# Isolated_DMX_Module.net
KiCad netlist of a schematic drawn in EAGLE
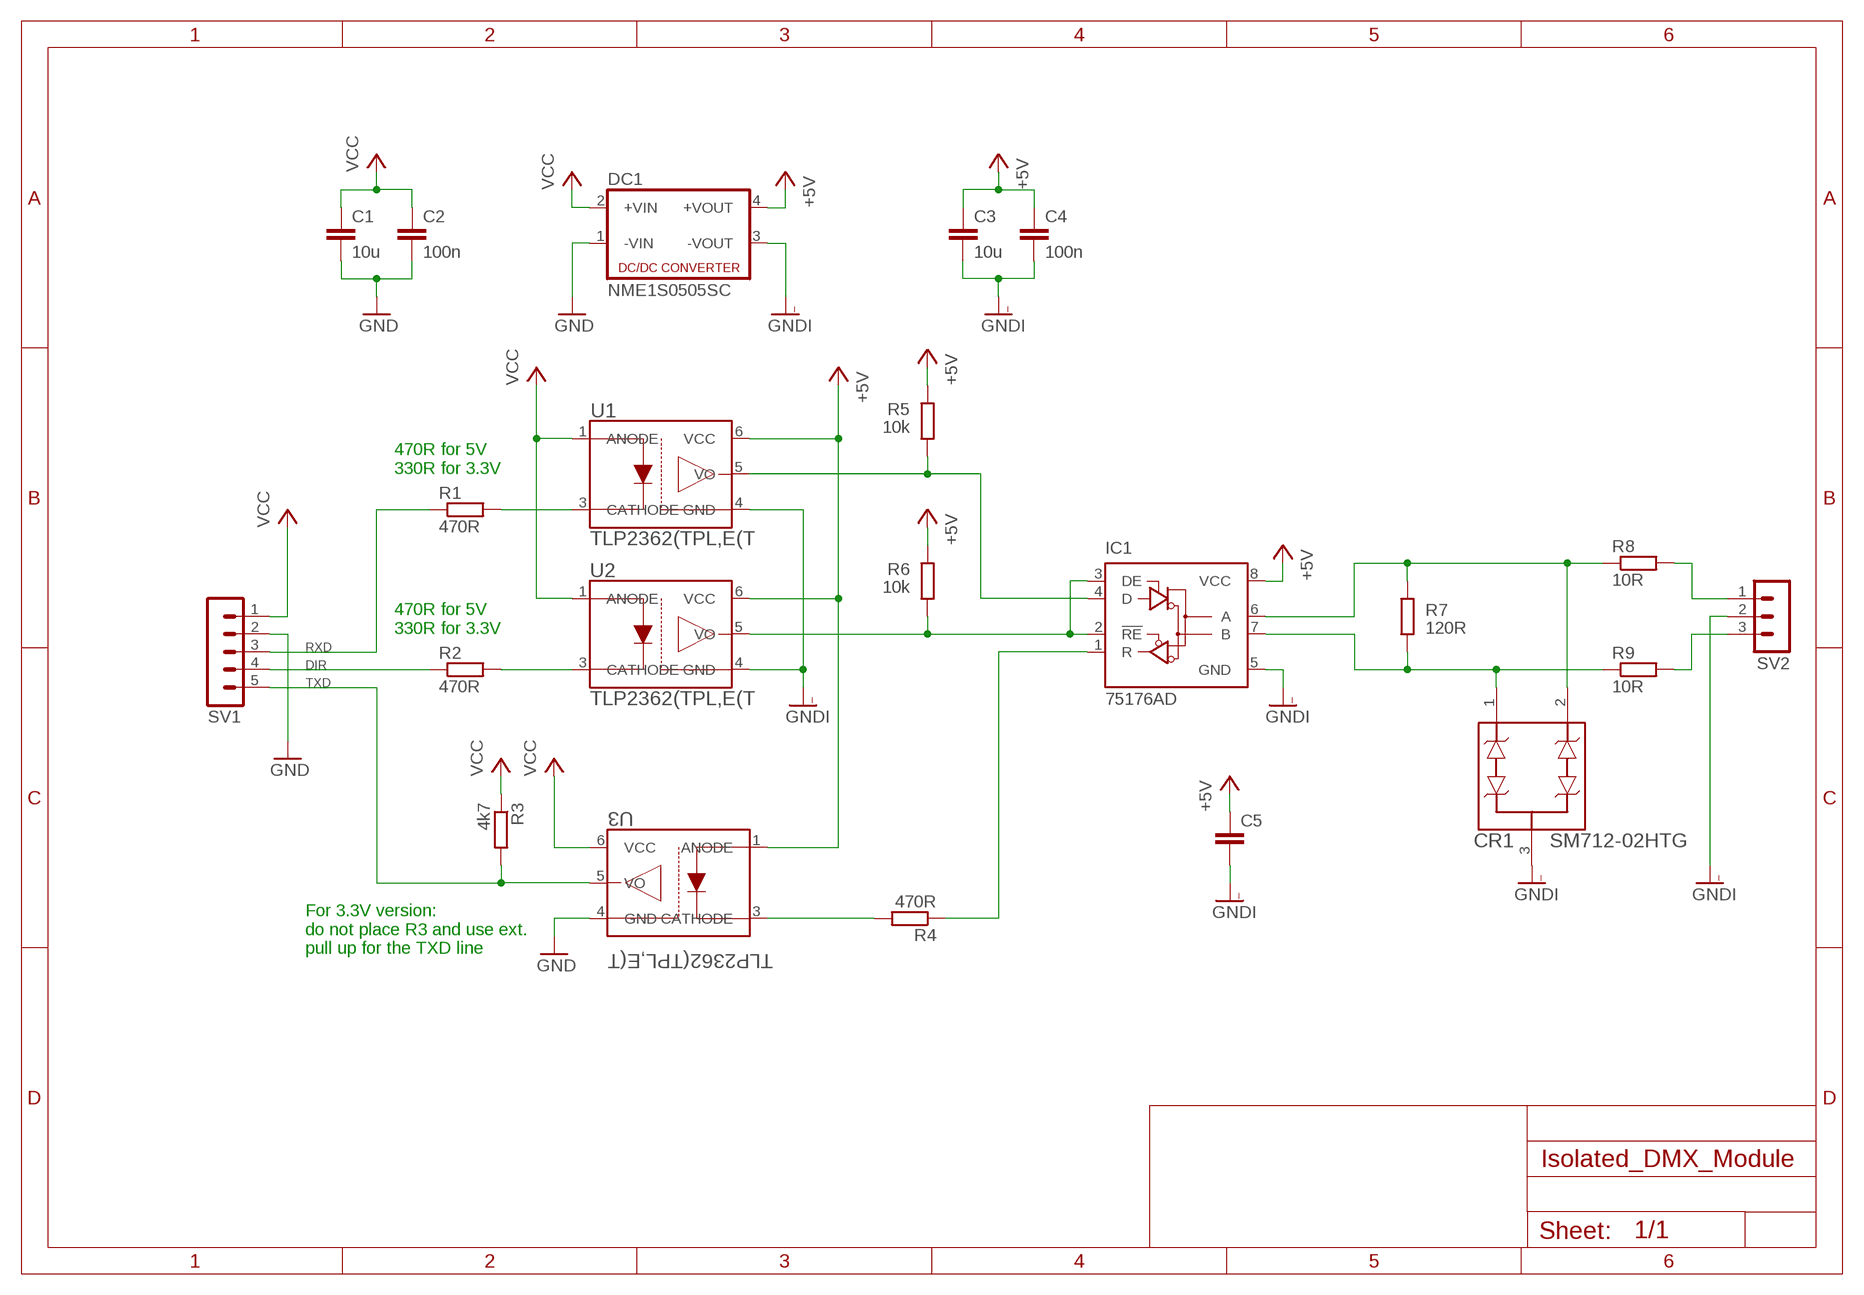
[diagram p0: schematic, sheet 1]

(export (version "E")
  (design (tool "Eeschema 10.0.6"))
  (components
    (comp (ref "C1")
      (value "10u")
      (footprint "eagle-import:C0805")
      (libsource (lib "eagle-import") (part "C-EUC0805"))
    )
    (comp (ref "C2")
      (value "100n")
      (footprint "eagle-import:C0603")
      (libsource (lib "eagle-import") (part "C-EUC0603"))
    )
    (comp (ref "C3")
      (value "10u")
      (footprint "eagle-import:C0805")
      (libsource (lib "eagle-import") (part "C-EUC0805"))
    )
    (comp (ref "C4")
      (value "100n")
      (footprint "eagle-import:C0603")
      (libsource (lib "eagle-import") (part "C-EUC0603"))
    )
    (comp (ref "C5")
      (value "C-EUC0603")
      (footprint "eagle-import:C0603")
      (libsource (lib "eagle-import") (part "C-EUC0603"))
    )
    (comp (ref "CR1")
      (value "SM712-02HTG")
      (footprint "eagle-import:SOT23-3_LTF")
      (fields (field (name "COPYRIGHT") "Copyright (C) 2024 Ultra Librarian. All rights reserved."))
      (libsource (lib "eagle-import") (part "SM712-02HTG"))
    )
    (comp (ref "DC1")
      (value "NME1S0505SC")
      (footprint "eagle-import:NME_FLAT")
      (libsource (lib "eagle-import") (part "NMEFLAT"))
    )
    (comp (ref "IC1")
      (value "75176AD")
      (footprint "eagle-import:D_R-PDSO-G8")
      (libsource (lib "eagle-import") (part "75176AD"))
    )
    (comp (ref "R1")
      (value "470R")
      (footprint "eagle-import:R0603")
      (libsource (lib "eagle-import") (part "R-EU_R0603"))
    )
    (comp (ref "R2")
      (value "470R")
      (footprint "eagle-import:R0603")
      (libsource (lib "eagle-import") (part "R-EU_R0603"))
    )
    (comp (ref "R3")
      (value "4k7")
      (footprint "eagle-import:R0603")
      (libsource (lib "eagle-import") (part "R-EU_R0603"))
    )
    (comp (ref "R4")
      (value "470R")
      (footprint "eagle-import:R0603")
      (libsource (lib "eagle-import") (part "R-EU_R0603"))
    )
    (comp (ref "R5")
      (value "10k")
      (footprint "eagle-import:R0603")
      (libsource (lib "eagle-import") (part "R-EU_R0603"))
    )
    (comp (ref "R6")
      (value "10k")
      (footprint "eagle-import:R0603")
      (libsource (lib "eagle-import") (part "R-EU_R0603"))
    )
    (comp (ref "R7")
      (value "120R")
      (footprint "eagle-import:R0603")
      (libsource (lib "eagle-import") (part "R-EU_R0603"))
    )
    (comp (ref "R8")
      (value "10R")
      (footprint "eagle-import:R0603")
      (libsource (lib "eagle-import") (part "R-EU_R0603"))
    )
    (comp (ref "R9")
      (value "10R")
      (footprint "eagle-import:R0603")
      (libsource (lib "eagle-import") (part "R-EU_R0603"))
    )
    (comp (ref "SV1")
      (value "MA05-1")
      (footprint "eagle-import:MA05-1")
      (libsource (lib "eagle-import") (part "MA05-1"))
    )
    (comp (ref "SV2")
      (value "MA03-1")
      (footprint "eagle-import:MA03-1")
      (libsource (lib "eagle-import") (part "MA03-1"))
    )
    (comp (ref "U1")
      (value "TLP2362(TPL,E(T")
      (footprint "eagle-import:11-4L1S_TOS")
      (fields (field (name "COPYRIGHT") "Copyright (C) 2024 Ultra Librarian. All rights reserved."))
      (libsource (lib "eagle-import") (part "TLP2362(TPL,E(T"))
    )
    (comp (ref "U2")
      (value "TLP2362(TPL,E(T")
      (footprint "eagle-import:11-4L1S_TOS")
      (fields (field (name "COPYRIGHT") "Copyright (C) 2024 Ultra Librarian. All rights reserved."))
      (libsource (lib "eagle-import") (part "TLP2362(TPL,E(T"))
    )
    (comp (ref "U3")
      (value "TLP2362(TPL,E(T")
      (footprint "eagle-import:11-4L1S_TOS")
      (fields (field (name "COPYRIGHT") "Copyright (C) 2024 Ultra Librarian. All rights reserved."))
      (libsource (lib "eagle-import") (part "TLP2362(TPL,E(T"))
    )
  )
  (nets
    (net (code "1") (name "+5V") (class "Default")
      (node (ref "C3") (pin "1") (pinfunction "1_1") (pintype "passive"))
      (node (ref "C4") (pin "1") (pinfunction "1_1") (pintype "passive"))
      (node (ref "C5") (pin "1") (pinfunction "1_1") (pintype "passive"))
      (node (ref "DC1") (pin "4") (pinfunction "+VOUT_4") (pintype "passive"))
      (node (ref "IC1") (pin "8") (pinfunction "VCC_8") (pintype "power_in"))
      (node (ref "R5") (pin "1") (pinfunction "1_1") (pintype "passive"))
      (node (ref "R6") (pin "1") (pinfunction "1_1") (pintype "passive"))
      (node (ref "U1") (pin "6") (pinfunction "VCC_6") (pintype "power_in"))
      (node (ref "U2") (pin "6") (pinfunction "VCC_6") (pintype "power_in"))
      (node (ref "U3") (pin "1") (pinfunction "ANODE_1") (pintype "passive"))
    )
    (net (code "2") (name "/DIR") (class "Default")
      (node (ref "R2") (pin "1") (pinfunction "1_1") (pintype "passive"))
      (node (ref "SV1") (pin "4") (pinfunction "4_4") (pintype "passive"))
    )
    (net (code "3") (name "/RXD") (class "Default")
      (node (ref "R1") (pin "1") (pinfunction "1_1") (pintype "passive"))
      (node (ref "SV1") (pin "3") (pinfunction "3_3") (pintype "passive"))
    )
    (net (code "4") (name "/TXD") (class "Default")
      (node (ref "R3") (pin "2") (pinfunction "2_2") (pintype "passive"))
      (node (ref "SV1") (pin "5") (pinfunction "5_5") (pintype "passive"))
      (node (ref "U3") (pin "5") (pinfunction "VO_5") (pintype "power_in"))
    )
    (net (code "5") (name "GND") (class "Default")
      (node (ref "C1") (pin "2") (pinfunction "2_2") (pintype "passive"))
      (node (ref "C2") (pin "2") (pinfunction "2_2") (pintype "passive"))
      (node (ref "DC1") (pin "1") (pinfunction "-VIN_1") (pintype "passive"))
      (node (ref "SV1") (pin "2") (pinfunction "2_2") (pintype "passive"))
      (node (ref "U3") (pin "4") (pinfunction "GND_4") (pintype "passive"))
    )
    (net (code "6") (name "GNDI") (class "Default")
      (node (ref "C3") (pin "2") (pinfunction "2_2") (pintype "passive"))
      (node (ref "C4") (pin "2") (pinfunction "2_2") (pintype "passive"))
      (node (ref "C5") (pin "2") (pinfunction "2_2") (pintype "passive"))
      (node (ref "CR1") (pin "3") (pinfunction "3_3") (pintype "passive"))
      (node (ref "DC1") (pin "3") (pinfunction "-VOUT_3") (pintype "passive"))
      (node (ref "IC1") (pin "5") (pinfunction "GND_5") (pintype "power_in"))
      (node (ref "SV2") (pin "2") (pinfunction "2_2") (pintype "passive"))
      (node (ref "U1") (pin "4") (pinfunction "GND_4") (pintype "passive"))
      (node (ref "U2") (pin "4") (pinfunction "GND_4") (pintype "passive"))
    )
    (net (code "7") (name "Net-(IC1-A)") (class "Default")
      (node (ref "CR1") (pin "2") (pinfunction "2_2") (pintype "passive"))
      (node (ref "IC1") (pin "6") (pinfunction "A_6") (pintype "output"))
      (node (ref "R7") (pin "1") (pinfunction "1_1") (pintype "passive"))
      (node (ref "R8") (pin "1") (pinfunction "1_1") (pintype "passive"))
    )
    (net (code "8") (name "Net-(IC1-B)") (class "Default")
      (node (ref "CR1") (pin "1") (pinfunction "1_1") (pintype "passive"))
      (node (ref "IC1") (pin "7") (pinfunction "B_7") (pintype "output"))
      (node (ref "R7") (pin "2") (pinfunction "2_2") (pintype "passive"))
      (node (ref "R9") (pin "1") (pinfunction "1_1") (pintype "passive"))
    )
    (net (code "9") (name "Net-(IC1-D)") (class "Default")
      (node (ref "IC1") (pin "4") (pinfunction "D_4") (pintype "input"))
      (node (ref "R5") (pin "2") (pinfunction "2_2") (pintype "passive"))
      (node (ref "U1") (pin "5") (pinfunction "VO_5") (pintype "power_in"))
    )
    (net (code "10") (name "Net-(IC1-DE)") (class "Default")
      (node (ref "IC1") (pin "2") (pinfunction "~{RE}_2") (pintype "input"))
      (node (ref "IC1") (pin "3") (pinfunction "DE_3") (pintype "input"))
      (node (ref "R6") (pin "2") (pinfunction "2_2") (pintype "passive"))
      (node (ref "U2") (pin "5") (pinfunction "VO_5") (pintype "power_in"))
    )
    (net (code "11") (name "Net-(IC1-R)") (class "Default")
      (node (ref "IC1") (pin "1") (pinfunction "R_1") (pintype "input"))
      (node (ref "R4") (pin "1") (pinfunction "1_1") (pintype "passive"))
    )
    (net (code "12") (name "Net-(R8-Pad2)") (class "Default")
      (node (ref "R8") (pin "2") (pinfunction "2_2") (pintype "passive"))
      (node (ref "SV2") (pin "1") (pinfunction "1_1") (pintype "passive"))
    )
    (net (code "13") (name "Net-(R9-Pad2)") (class "Default")
      (node (ref "R9") (pin "2") (pinfunction "2_2") (pintype "passive"))
      (node (ref "SV2") (pin "3") (pinfunction "3_3") (pintype "passive"))
    )
    (net (code "14") (name "Net-(U1-CATHODE)") (class "Default")
      (node (ref "R1") (pin "2") (pinfunction "2_2") (pintype "passive"))
      (node (ref "U1") (pin "3") (pinfunction "CATHODE_3") (pintype "passive"))
    )
    (net (code "15") (name "Net-(U2-CATHODE)") (class "Default")
      (node (ref "R2") (pin "2") (pinfunction "2_2") (pintype "passive"))
      (node (ref "U2") (pin "3") (pinfunction "CATHODE_3") (pintype "passive"))
    )
    (net (code "16") (name "Net-(U3-CATHODE)") (class "Default")
      (node (ref "R4") (pin "2") (pinfunction "2_2") (pintype "passive"))
      (node (ref "U3") (pin "3") (pinfunction "CATHODE_3") (pintype "passive"))
    )
    (net (code "17") (name "VCC") (class "Default")
      (node (ref "C1") (pin "1") (pinfunction "1_1") (pintype "passive"))
      (node (ref "C2") (pin "1") (pinfunction "1_1") (pintype "passive"))
      (node (ref "DC1") (pin "2") (pinfunction "+VIN_2") (pintype "passive"))
      (node (ref "R3") (pin "1") (pinfunction "1_1") (pintype "passive"))
      (node (ref "SV1") (pin "1") (pinfunction "1_1") (pintype "passive"))
      (node (ref "U1") (pin "1") (pinfunction "ANODE_1") (pintype "passive"))
      (node (ref "U2") (pin "1") (pinfunction "ANODE_1") (pintype "passive"))
      (node (ref "U3") (pin "6") (pinfunction "VCC_6") (pintype "power_in"))
    )
  )
)
